# RCReceiver.net
KiCad netlist of a schematic drawn in Altium Designer
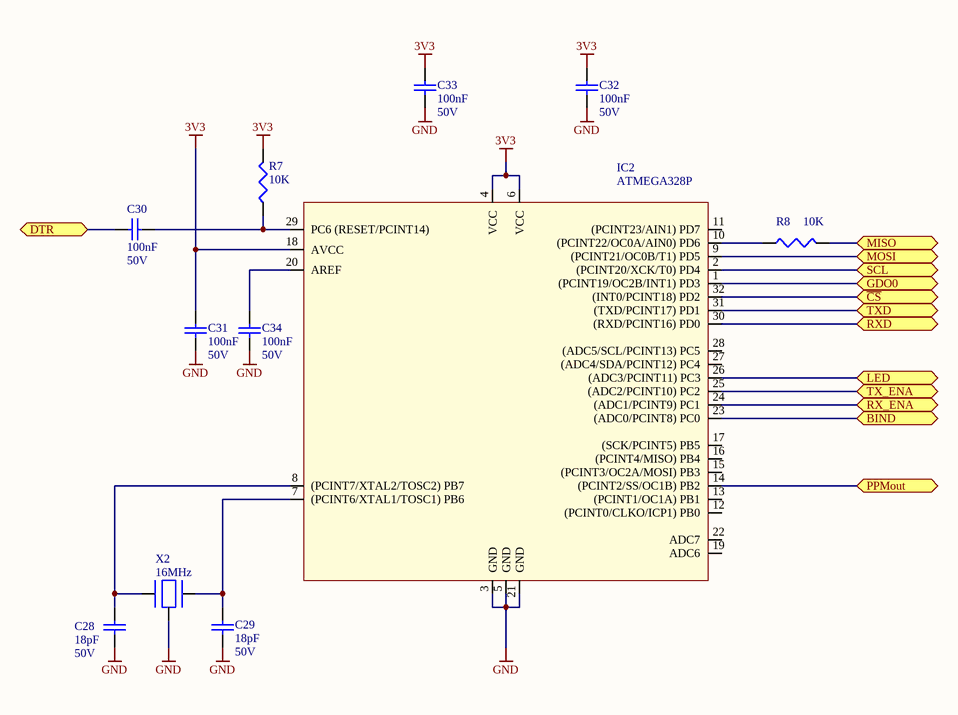
[diagram p0: RCReceiver.SchDoc]

(export (version "E")
  (design (tool "Eeschema 10.0.6"))
  (components
    (comp (ref "C28")
      (value "18pF")
      (footprint "C0603")
      (description "Capacitor, 18pF, 50V, C0G / NP0")
      (fields (field (name "VOLTAGE RATING") "50V"))
      (libsource (lib "AR_Capacitors_Ceramic") (part "18pF/0603/CER/50V"))
    )
    (comp (ref "C29")
      (value "18pF")
      (footprint "C0603")
      (description "Capacitor, 18pF, 50V, C0G / NP0")
      (fields (field (name "VOLTAGE RATING") "50V"))
      (libsource (lib "AR_Capacitors_Ceramic") (part "18pF/0603/CER/50V"))
    )
    (comp (ref "C30")
      (value "100nF")
      (footprint "C0603")
      (description "Capacitor, 100nF, 50V, X7R")
      (fields (field (name "VOLTAGE RATING") "50V"))
      (libsource (lib "AR_Capacitors_Ceramic") (part "100nF/0603/CER/50V"))
    )
    (comp (ref "C31")
      (value "100nF")
      (footprint "C0603")
      (description "Capacitor, 100nF, 50V, X7R")
      (fields (field (name "VOLTAGE RATING") "50V"))
      (libsource (lib "AR_Capacitors_Ceramic") (part "100nF/0603/CER/50V"))
    )
    (comp (ref "C32")
      (value "100nF")
      (footprint "C0603")
      (description "Capacitor, 100nF, 50V, X7R")
      (fields (field (name "VOLTAGE RATING") "50V"))
      (libsource (lib "AR_Capacitors_Ceramic") (part "100nF/0603/CER/50V"))
    )
    (comp (ref "C33")
      (value "100nF")
      (footprint "C0603")
      (description "Capacitor, 100nF, 50V, X7R")
      (fields (field (name "VOLTAGE RATING") "50V"))
      (libsource (lib "AR_Capacitors_Ceramic") (part "100nF/0603/CER/50V"))
    )
    (comp (ref "C34")
      (value "100nF")
      (footprint "C0603")
      (description "Capacitor, 100nF, 50V, X7R")
      (fields (field (name "VOLTAGE RATING") "50V"))
      (libsource (lib "AR_Capacitors_Ceramic") (part "100nF/0603/CER/50V"))
    )
    (comp (ref "IC2")
      (value "ATMEGA328P")
      (footprint "LFCSP32")
      (description "8-Bit microcontroller ATMEL")
      (libsource (lib "AR_Microcontrollers") (part "ATMEGA328P"))
    )
    (comp (ref "R7")
      (value "10K")
      (footprint "0603")
      (description "Resistor, 10K, 1%, 0.063W, 50V, 100PPM, 0603")
      (libsource (lib "AR_Resistors_SMD") (part "10K/0603/0063W/50V"))
    )
    (comp (ref "R8")
      (value "10K")
      (footprint "0603")
      (description "Resistor, 10K, 1%, 0.063W, 50V, 100PPM, 0603")
      (libsource (lib "AR_Resistors_SMD") (part "10K/0603/0063W/50V"))
    )
    (comp (ref "X2")
      (value "16MHz")
      (footprint "7M")
      (description "CRYSTAL, 16MHz,18PF CL, 3.2X2.5MM SMT")
      (libsource (lib "AR_Crystals") (part "7M-16.000MAAJ-T"))
    )
  )
  (nets
    (net (code "1") (name "/BIND") (class "Default")
      (node (ref "IC2") (pin "23") (pinfunction "(ADC0/PCINT8)_PC0_23") (pintype "bidirectional"))
    )
    (net (code "2") (name "/DTR") (class "Default")
      (node (ref "C30") (pin "1") (pinfunction "1_1") (pintype "passive"))
    )
    (net (code "3") (name "/GDO0") (class "Default")
      (node (ref "IC2") (pin "1") (pinfunction "(PCINT19/OC2B/INT1)_PD3_1") (pintype "bidirectional"))
    )
    (net (code "4") (name "/LED") (class "Default")
      (node (ref "IC2") (pin "26") (pinfunction "(ADC3/PCINT11)_PC3_26") (pintype "bidirectional"))
    )
    (net (code "5") (name "/MISO") (class "Default")
      (node (ref "R8") (pin "2") (pinfunction "2_2") (pintype "passive"))
    )
    (net (code "6") (name "/MOSI") (class "Default")
      (node (ref "IC2") (pin "9") (pinfunction "(PCINT21/OC0B/T1)_PD5_9") (pintype "bidirectional"))
    )
    (net (code "7") (name "/PPMout") (class "Default")
      (node (ref "IC2") (pin "14") (pinfunction "(PCINT2/SS/OC1B)_PB2_14") (pintype "bidirectional"))
    )
    (net (code "8") (name "/RXD") (class "Default")
      (node (ref "IC2") (pin "30") (pinfunction "(RXD/PCINT16)_PD0_30") (pintype "bidirectional"))
    )
    (net (code "9") (name "/RX_ENA") (class "Default")
      (node (ref "IC2") (pin "24") (pinfunction "(ADC1/PCINT9)_PC1_24") (pintype "bidirectional"))
    )
    (net (code "10") (name "/SCL") (class "Default")
      (node (ref "IC2") (pin "2") (pinfunction "(PCINT20/XCK/T0)_PD4_2") (pintype "bidirectional"))
    )
    (net (code "11") (name "/TXD") (class "Default")
      (node (ref "IC2") (pin "31") (pinfunction "(TXD/PCINT17)_PD1_31") (pintype "bidirectional"))
    )
    (net (code "12") (name "/TX_ENA") (class "Default")
      (node (ref "IC2") (pin "25") (pinfunction "(ADC2/PCINT10)_PC2_25") (pintype "bidirectional"))
    )
    (net (code "13") (name "/~{CS}") (class "Default")
      (node (ref "IC2") (pin "32") (pinfunction "(INT0/PCINT18)_PD2_32") (pintype "bidirectional"))
    )
    (net (code "14") (name "3V3") (class "Default")
      (node (ref "C31") (pin "2") (pinfunction "2_2") (pintype "passive"))
      (node (ref "C32") (pin "2") (pinfunction "2_2") (pintype "passive"))
      (node (ref "C33") (pin "2") (pinfunction "2_2") (pintype "passive"))
      (node (ref "IC2") (pin "18") (pinfunction "AVCC_18") (pintype "power_in"))
      (node (ref "IC2") (pin "4") (pinfunction "VCC_4") (pintype "power_in"))
      (node (ref "IC2") (pin "6") (pinfunction "VCC_6") (pintype "power_in"))
      (node (ref "R7") (pin "2") (pinfunction "2_2") (pintype "passive"))
    )
    (net (code "15") (name "GND") (class "Default")
      (node (ref "C28") (pin "1") (pinfunction "1_1") (pintype "passive"))
      (node (ref "C29") (pin "1") (pinfunction "1_1") (pintype "passive"))
      (node (ref "C31") (pin "1") (pinfunction "1_1") (pintype "passive"))
      (node (ref "C32") (pin "1") (pinfunction "1_1") (pintype "passive"))
      (node (ref "C33") (pin "1") (pinfunction "1_1") (pintype "passive"))
      (node (ref "C34") (pin "1") (pinfunction "1_1") (pintype "passive"))
      (node (ref "IC2") (pin "21") (pinfunction "GND_21") (pintype "power_in"))
      (node (ref "IC2") (pin "3") (pinfunction "GND_3") (pintype "power_in"))
      (node (ref "IC2") (pin "5") (pinfunction "GND_5") (pintype "power_in"))
      (node (ref "X2") (pin "0") (pinfunction "0_0") (pintype "power_in"))
    )
    (net (code "16") (name "Net-(IC2-(PCINT6{slash}XTAL1{slash}TOSC1)_PB6)") (class "Default")
      (node (ref "C29") (pin "2") (pinfunction "2_2") (pintype "passive"))
      (node (ref "IC2") (pin "7") (pinfunction "(PCINT6/XTAL1/TOSC1)_PB6_7") (pintype "bidirectional"))
      (node (ref "X2") (pin "2") (pinfunction "2_2") (pintype "passive"))
    )
    (net (code "17") (name "Net-(IC2-(PCINT7{slash}XTAL2{slash}TOSC2)_PB7)") (class "Default")
      (node (ref "C28") (pin "2") (pinfunction "2_2") (pintype "passive"))
      (node (ref "IC2") (pin "8") (pinfunction "(PCINT7/XTAL2/TOSC2)_PB7_8") (pintype "bidirectional"))
      (node (ref "X2") (pin "1") (pinfunction "1_1") (pintype "passive"))
    )
    (net (code "18") (name "Net-(IC2-(PCINT22{slash}OC0A{slash}AIN0)_PD6)") (class "Default")
      (node (ref "IC2") (pin "10") (pinfunction "(PCINT22/OC0A/AIN0)_PD6_10") (pintype "bidirectional"))
      (node (ref "R8") (pin "1") (pinfunction "1_1") (pintype "passive"))
    )
    (net (code "19") (name "Net-(IC2-AREF)") (class "Default")
      (node (ref "C34") (pin "2") (pinfunction "2_2") (pintype "passive"))
      (node (ref "IC2") (pin "20") (pinfunction "AREF_20") (pintype "power_in"))
    )
    (net (code "20") (name "Net-(IC2-PC6_(RESET{slash}PCINT14))") (class "Default")
      (node (ref "C30") (pin "2") (pinfunction "2_2") (pintype "passive"))
      (node (ref "IC2") (pin "29") (pinfunction "PC6_(RESET/PCINT14)_29") (pintype "bidirectional"))
      (node (ref "R7") (pin "1") (pinfunction "1_1") (pintype "passive"))
    )
    (net (code "21") (name "unconnected-(IC2-(ADC4{slash}SDA{slash}PCINT12)_PC4-Pad27)") (class "Default")
      (node (ref "IC2") (pin "27") (pinfunction "(ADC4/SDA/PCINT12)_PC4_27") (pintype "bidirectional"))
    )
    (net (code "22") (name "unconnected-(IC2-(ADC5{slash}SCL{slash}PCINT13)_PC5-Pad28)") (class "Default")
      (node (ref "IC2") (pin "28") (pinfunction "(ADC5/SCL/PCINT13)_PC5_28") (pintype "bidirectional"))
    )
    (net (code "23") (name "unconnected-(IC2-(PCINT0{slash}CLKO{slash}ICP1)_PB0-Pad12)") (class "Default")
      (node (ref "IC2") (pin "12") (pinfunction "(PCINT0/CLKO/ICP1)_PB0_12") (pintype "bidirectional"))
    )
    (net (code "24") (name "unconnected-(IC2-(PCINT1{slash}OC1A)_PB1-Pad13)") (class "Default")
      (node (ref "IC2") (pin "13") (pinfunction "(PCINT1/OC1A)_PB1_13") (pintype "bidirectional"))
    )
    (net (code "25") (name "unconnected-(IC2-(PCINT3{slash}OC2A{slash}MOSI)_PB3-Pad15)") (class "Default")
      (node (ref "IC2") (pin "15") (pinfunction "(PCINT3/OC2A/MOSI)_PB3_15") (pintype "bidirectional"))
    )
    (net (code "26") (name "unconnected-(IC2-(PCINT4{slash}MISO)_PB4-Pad16)") (class "Default")
      (node (ref "IC2") (pin "16") (pinfunction "(PCINT4/MISO)_PB4_16") (pintype "bidirectional"))
    )
    (net (code "27") (name "unconnected-(IC2-(PCINT23{slash}AIN1)_PD7-Pad11)") (class "Default")
      (node (ref "IC2") (pin "11") (pinfunction "(PCINT23/AIN1)_PD7_11") (pintype "bidirectional"))
    )
    (net (code "28") (name "unconnected-(IC2-(SCK{slash}PCINT5)_PB5-Pad17)") (class "Default")
      (node (ref "IC2") (pin "17") (pinfunction "(SCK/PCINT5)_PB5_17") (pintype "bidirectional"))
    )
    (net (code "29") (name "unconnected-(IC2-ADC6-Pad19)") (class "Default")
      (node (ref "IC2") (pin "19") (pinfunction "ADC6_19") (pintype "power_in"))
    )
    (net (code "30") (name "unconnected-(IC2-ADC7-Pad22)") (class "Default")
      (node (ref "IC2") (pin "22") (pinfunction "ADC7_22") (pintype "power_in"))
    )
  )
)
